# Battery_supply.net
KiCad netlist of a schematic drawn in Altium Designer
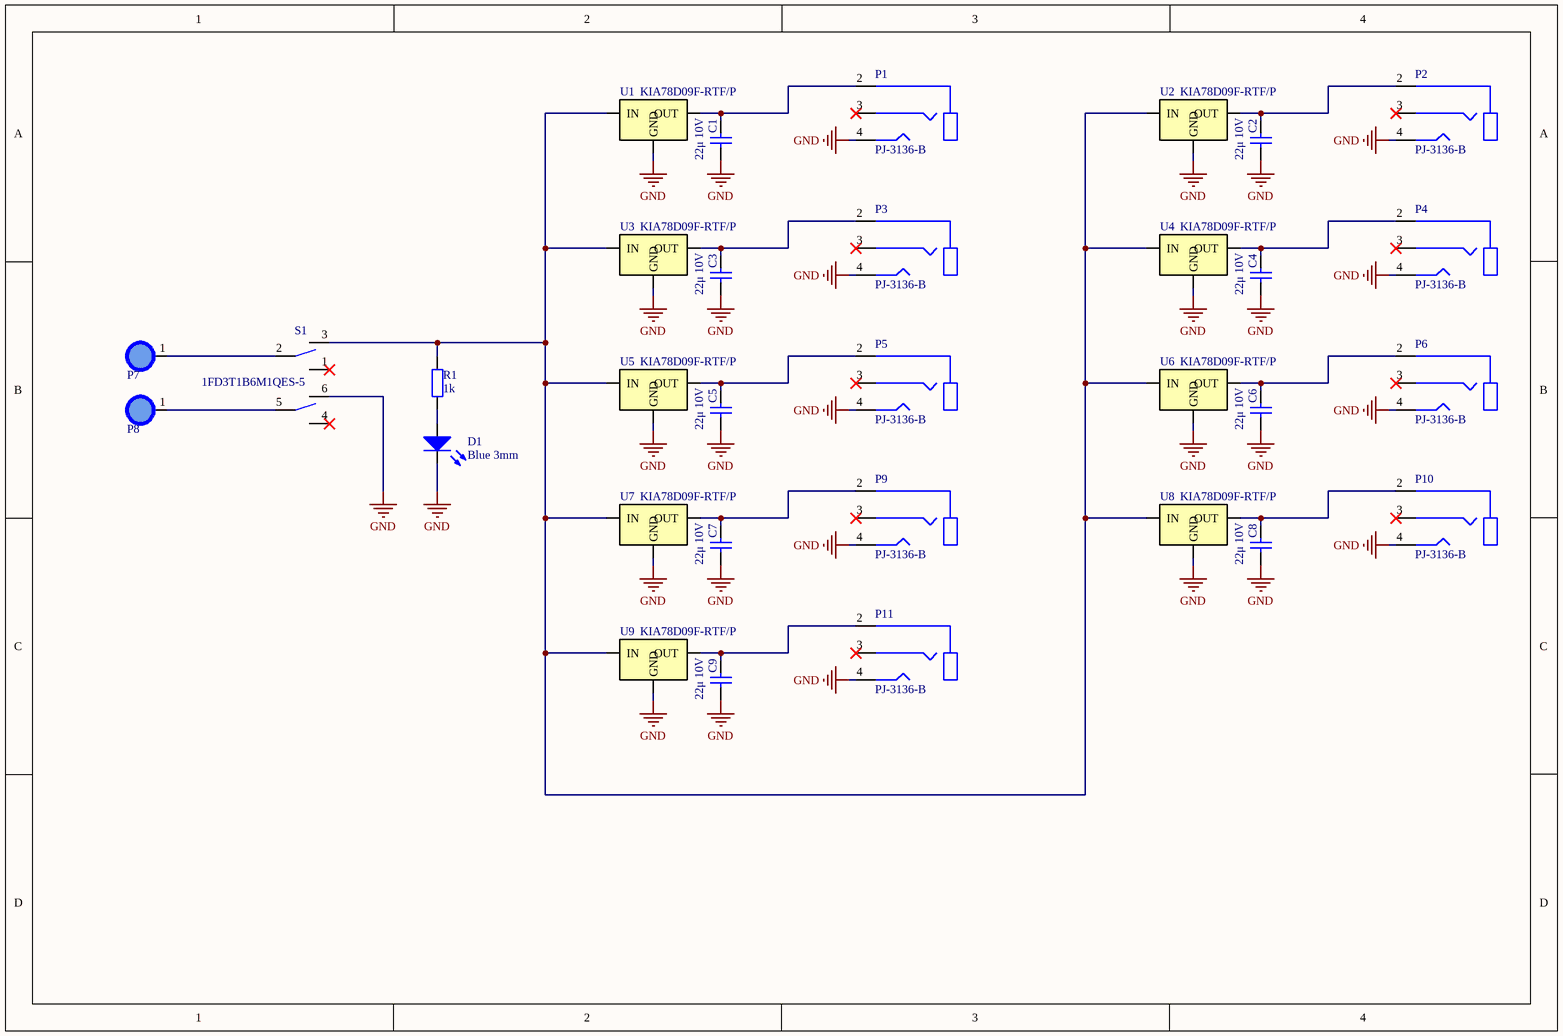
[diagram p0: Battery supply.SchDoc]

(export (version "E")
  (design (tool "Eeschema 10.0.6"))
  (components
    (comp (ref "C1")
      (value "22μ 10V")
      (footprint "Battery supply:Capacitor 0603")
      (description "X5R ±20% 10V 22uF 0603 Multilayer Ceramic Capacitors MLCC - SMD/SMT ROHS")
      (fields (field (name "MFR. PART #") "0603X226M100NT") (field (name "LCSC PART #") "C60077"))
      (libsource (lib "Battery supply") (part "Capacitor 22μF 0603 ±10% 10V"))
    )
    (comp (ref "C2")
      (value "22μ 10V")
      (footprint "Battery supply:Capacitor 0603")
      (description "X5R ±20% 10V 22uF 0603 Multilayer Ceramic Capacitors MLCC - SMD/SMT ROHS")
      (fields (field (name "MFR. PART #") "0603X226M100NT") (field (name "LCSC PART #") "C60077"))
      (libsource (lib "Battery supply") (part "Capacitor 22μF 0603 ±10% 10V"))
    )
    (comp (ref "C3")
      (value "22μ 10V")
      (footprint "Battery supply:Capacitor 0603")
      (description "X5R ±20% 10V 22uF 0603 Multilayer Ceramic Capacitors MLCC - SMD/SMT ROHS")
      (fields (field (name "MFR. PART #") "0603X226M100NT") (field (name "LCSC PART #") "C60077"))
      (libsource (lib "Battery supply") (part "Capacitor 22μF 0603 ±10% 10V"))
    )
    (comp (ref "C4")
      (value "22μ 10V")
      (footprint "Battery supply:Capacitor 0603")
      (description "X5R ±20% 10V 22uF 0603 Multilayer Ceramic Capacitors MLCC - SMD/SMT ROHS")
      (fields (field (name "MFR. PART #") "0603X226M100NT") (field (name "LCSC PART #") "C60077"))
      (libsource (lib "Battery supply") (part "Capacitor 22μF 0603 ±10% 10V"))
    )
    (comp (ref "C5")
      (value "22μ 10V")
      (footprint "Battery supply:Capacitor 0603")
      (description "X5R ±20% 10V 22uF 0603 Multilayer Ceramic Capacitors MLCC - SMD/SMT ROHS")
      (fields (field (name "MFR. PART #") "0603X226M100NT") (field (name "LCSC PART #") "C60077"))
      (libsource (lib "Battery supply") (part "Capacitor 22μF 0603 ±10% 10V"))
    )
    (comp (ref "C6")
      (value "22μ 10V")
      (footprint "Battery supply:Capacitor 0603")
      (description "X5R ±20% 10V 22uF 0603 Multilayer Ceramic Capacitors MLCC - SMD/SMT ROHS")
      (fields (field (name "MFR. PART #") "0603X226M100NT") (field (name "LCSC PART #") "C60077"))
      (libsource (lib "Battery supply") (part "Capacitor 22μF 0603 ±10% 10V"))
    )
    (comp (ref "C7")
      (value "22μ 10V")
      (footprint "Battery supply:Capacitor 0603")
      (description "X5R ±20% 10V 22uF 0603 Multilayer Ceramic Capacitors MLCC - SMD/SMT ROHS")
      (fields (field (name "MFR. PART #") "0603X226M100NT") (field (name "LCSC PART #") "C60077"))
      (libsource (lib "Battery supply") (part "Capacitor 22μF 0603 ±10% 10V"))
    )
    (comp (ref "C8")
      (value "22μ 10V")
      (footprint "Battery supply:Capacitor 0603")
      (description "X5R ±20% 10V 22uF 0603 Multilayer Ceramic Capacitors MLCC - SMD/SMT ROHS")
      (fields (field (name "MFR. PART #") "0603X226M100NT") (field (name "LCSC PART #") "C60077"))
      (libsource (lib "Battery supply") (part "Capacitor 22μF 0603 ±10% 10V"))
    )
    (comp (ref "C9")
      (value "22μ 10V")
      (footprint "Battery supply:Capacitor 0603")
      (description "X5R ±20% 10V 22uF 0603 Multilayer Ceramic Capacitors MLCC - SMD/SMT ROHS")
      (fields (field (name "MFR. PART #") "0603X226M100NT") (field (name "LCSC PART #") "C60077"))
      (libsource (lib "Battery supply") (part "Capacitor 22μF 0603 ±10% 10V"))
    )
    (comp (ref "D1")
      (value "Blue 3mm")
      (footprint "Battery supply:LED 3MM BLUE")
      (description "Blue 460nm~470nm 2.7V~3.6V Through Hole Light Emitting Diodes (LED) ROHS")
      (fields (field (name "MFR. PART #") "TJ-L3FYTGCBMCGSFLC6B-A5") (field (name "LCSC PART #") "C330760"))
      (libsource (lib "Battery supply") (part "Diode LED Blue 3mm THT"))
    )
    (comp (ref "P1")
      (value "PJ-3136-B")
      (footprint "Battery supply:PJ-3136-B")
      (description "3.5mm Plug-in headphone holder Horizontal 6 Female DIP Audio & Video Connectors ROHS")
      (fields (field (name "LCSC PART #") "C381131"))
      (libsource (lib "Battery supply") (part "Mechanical Headphone Holder JACK PJ-3136-B"))
    )
    (comp (ref "P2")
      (value "PJ-3136-B")
      (footprint "Battery supply:PJ-3136-B")
      (description "3.5mm Plug-in headphone holder Horizontal 6 Female DIP Audio & Video Connectors ROHS")
      (fields (field (name "LCSC PART #") "C381131"))
      (libsource (lib "Battery supply") (part "Mechanical Headphone Holder JACK PJ-3136-B"))
    )
    (comp (ref "P3")
      (value "PJ-3136-B")
      (footprint "Battery supply:PJ-3136-B")
      (description "3.5mm Plug-in headphone holder Horizontal 6 Female DIP Audio & Video Connectors ROHS")
      (fields (field (name "LCSC PART #") "C381131"))
      (libsource (lib "Battery supply") (part "Mechanical Headphone Holder JACK PJ-3136-B"))
    )
    (comp (ref "P4")
      (value "PJ-3136-B")
      (footprint "Battery supply:PJ-3136-B")
      (description "3.5mm Plug-in headphone holder Horizontal 6 Female DIP Audio & Video Connectors ROHS")
      (fields (field (name "LCSC PART #") "C381131"))
      (libsource (lib "Battery supply") (part "Mechanical Headphone Holder JACK PJ-3136-B"))
    )
    (comp (ref "P5")
      (value "PJ-3136-B")
      (footprint "Battery supply:PJ-3136-B")
      (description "3.5mm Plug-in headphone holder Horizontal 6 Female DIP Audio & Video Connectors ROHS")
      (fields (field (name "LCSC PART #") "C381131"))
      (libsource (lib "Battery supply") (part "Mechanical Headphone Holder JACK PJ-3136-B"))
    )
    (comp (ref "P6")
      (value "PJ-3136-B")
      (footprint "Battery supply:PJ-3136-B")
      (description "3.5mm Plug-in headphone holder Horizontal 6 Female DIP Audio & Video Connectors ROHS")
      (fields (field (name "LCSC PART #") "C381131"))
      (libsource (lib "Battery supply") (part "Mechanical Headphone Holder JACK PJ-3136-B"))
    )
    (comp (ref "P7")
      (value "PAd")
      (footprint "Battery supply:PAD")
      (description "Pad 1mm")
      (libsource (lib "Battery supply") (part "Mechanical PAD 1mm"))
    )
    (comp (ref "P8")
      (value "PAd")
      (footprint "Battery supply:PAD")
      (description "Pad 1mm")
      (libsource (lib "Battery supply") (part "Mechanical PAD 1mm"))
    )
    (comp (ref "P9")
      (value "PJ-3136-B")
      (footprint "Battery supply:PJ-3136-B")
      (description "3.5mm Plug-in headphone holder Horizontal 6 Female DIP Audio & Video Connectors ROHS")
      (fields (field (name "LCSC PART #") "C381131"))
      (libsource (lib "Battery supply") (part "Mechanical Headphone Holder JACK PJ-3136-B"))
    )
    (comp (ref "P10")
      (value "PJ-3136-B")
      (footprint "Battery supply:PJ-3136-B")
      (description "3.5mm Plug-in headphone holder Horizontal 6 Female DIP Audio & Video Connectors ROHS")
      (fields (field (name "LCSC PART #") "C381131"))
      (libsource (lib "Battery supply") (part "Mechanical Headphone Holder JACK PJ-3136-B"))
    )
    (comp (ref "P11")
      (value "PJ-3136-B")
      (footprint "Battery supply:PJ-3136-B")
      (description "3.5mm Plug-in headphone holder Horizontal 6 Female DIP Audio & Video Connectors ROHS")
      (fields (field (name "LCSC PART #") "C381131"))
      (libsource (lib "Battery supply") (part "Mechanical Headphone Holder JACK PJ-3136-B"))
    )
    (comp (ref "R1")
      (value "1k")
      (footprint "Battery supply:Resistor 0603")
      (description "±1% ±100ppm/℃ 1kΩ 0.1W 0603 Chip Resistor - Surface Mount ROHS")
      (fields (field (name "MFR. PART #") "RC0603FR-071KL") (field (name "LCSC PART #") "C22548"))
      (libsource (lib "Battery supply") (part "Resistor 1kΩ 0603 ±1% 0.1W"))
    )
    (comp (ref "S1")
      (value "1FD3T1B6M1QES-5")
      (footprint "Battery supply:1FD3T1B6M1QES-5")
      (description "H=10.5mm Toggle Switches ROHS")
      (fields (field (name "LCSC PART #") "C908278"))
      (libsource (lib "Battery supply") (part "Mechanical Toggle Switch ON-OFF-ON 1FD3T1B6M1QES-5"))
    )
    (comp (ref "U1")
      (value "KIA78D09F-RTF/P")
      (footprint "Battery supply:KIA78D09F-RTF/P")
      (description "25V 500mV @ 500mA Fixed 9V TO-252-2(DPAK) Linear Voltage Regulators (LDO) ROHS")
      (fields (field (name "LCSC PART #") "C69764"))
      (libsource (lib "Battery supply") (part "IC LDO 9V 500mA KIA78D09F-RTF/P"))
    )
    (comp (ref "U2")
      (value "KIA78D09F-RTF/P")
      (footprint "Battery supply:KIA78D09F-RTF/P")
      (description "25V 500mV @ 500mA Fixed 9V TO-252-2(DPAK) Linear Voltage Regulators (LDO) ROHS")
      (fields (field (name "LCSC PART #") "C69764"))
      (libsource (lib "Battery supply") (part "IC LDO 9V 500mA KIA78D09F-RTF/P"))
    )
    (comp (ref "U3")
      (value "KIA78D09F-RTF/P")
      (footprint "Battery supply:KIA78D09F-RTF/P")
      (description "25V 500mV @ 500mA Fixed 9V TO-252-2(DPAK) Linear Voltage Regulators (LDO) ROHS")
      (fields (field (name "LCSC PART #") "C69764"))
      (libsource (lib "Battery supply") (part "IC LDO 9V 500mA KIA78D09F-RTF/P"))
    )
    (comp (ref "U4")
      (value "KIA78D09F-RTF/P")
      (footprint "Battery supply:KIA78D09F-RTF/P")
      (description "25V 500mV @ 500mA Fixed 9V TO-252-2(DPAK) Linear Voltage Regulators (LDO) ROHS")
      (fields (field (name "LCSC PART #") "C69764"))
      (libsource (lib "Battery supply") (part "IC LDO 9V 500mA KIA78D09F-RTF/P"))
    )
    (comp (ref "U5")
      (value "KIA78D09F-RTF/P")
      (footprint "Battery supply:KIA78D09F-RTF/P")
      (description "25V 500mV @ 500mA Fixed 9V TO-252-2(DPAK) Linear Voltage Regulators (LDO) ROHS")
      (fields (field (name "LCSC PART #") "C69764"))
      (libsource (lib "Battery supply") (part "IC LDO 9V 500mA KIA78D09F-RTF/P"))
    )
    (comp (ref "U6")
      (value "KIA78D09F-RTF/P")
      (footprint "Battery supply:KIA78D09F-RTF/P")
      (description "25V 500mV @ 500mA Fixed 9V TO-252-2(DPAK) Linear Voltage Regulators (LDO) ROHS")
      (fields (field (name "LCSC PART #") "C69764"))
      (libsource (lib "Battery supply") (part "IC LDO 9V 500mA KIA78D09F-RTF/P"))
    )
    (comp (ref "U7")
      (value "KIA78D09F-RTF/P")
      (footprint "Battery supply:KIA78D09F-RTF/P")
      (description "25V 500mV @ 500mA Fixed 9V TO-252-2(DPAK) Linear Voltage Regulators (LDO) ROHS")
      (fields (field (name "LCSC PART #") "C69764"))
      (libsource (lib "Battery supply") (part "IC LDO 9V 500mA KIA78D09F-RTF/P"))
    )
    (comp (ref "U8")
      (value "KIA78D09F-RTF/P")
      (footprint "Battery supply:KIA78D09F-RTF/P")
      (description "25V 500mV @ 500mA Fixed 9V TO-252-2(DPAK) Linear Voltage Regulators (LDO) ROHS")
      (fields (field (name "LCSC PART #") "C69764"))
      (libsource (lib "Battery supply") (part "IC LDO 9V 500mA KIA78D09F-RTF/P"))
    )
    (comp (ref "U9")
      (value "KIA78D09F-RTF/P")
      (footprint "Battery supply:KIA78D09F-RTF/P")
      (description "25V 500mV @ 500mA Fixed 9V TO-252-2(DPAK) Linear Voltage Regulators (LDO) ROHS")
      (fields (field (name "LCSC PART #") "C69764"))
      (libsource (lib "Battery supply") (part "IC LDO 9V 500mA KIA78D09F-RTF/P"))
    )
  )
  (nets
    (net (code "1") (name "GND") (class "Default")
      (node (ref "C1") (pin "1") (pinfunction "1_1") (pintype "passive"))
      (node (ref "C2") (pin "1") (pinfunction "1_1") (pintype "passive"))
      (node (ref "C3") (pin "1") (pinfunction "1_1") (pintype "passive"))
      (node (ref "C4") (pin "1") (pinfunction "1_1") (pintype "passive"))
      (node (ref "C5") (pin "1") (pinfunction "1_1") (pintype "passive"))
      (node (ref "C6") (pin "1") (pinfunction "1_1") (pintype "passive"))
      (node (ref "C7") (pin "1") (pinfunction "1_1") (pintype "passive"))
      (node (ref "C8") (pin "1") (pinfunction "1_1") (pintype "passive"))
      (node (ref "C9") (pin "1") (pinfunction "1_1") (pintype "passive"))
      (node (ref "D1") (pin "1") (pinfunction "1_1") (pintype "passive"))
      (node (ref "P1") (pin "4") (pinfunction "4_4") (pintype "passive"))
      (node (ref "P10") (pin "4") (pinfunction "4_4") (pintype "passive"))
      (node (ref "P11") (pin "4") (pinfunction "4_4") (pintype "passive"))
      (node (ref "P2") (pin "4") (pinfunction "4_4") (pintype "passive"))
      (node (ref "P3") (pin "4") (pinfunction "4_4") (pintype "passive"))
      (node (ref "P4") (pin "4") (pinfunction "4_4") (pintype "passive"))
      (node (ref "P5") (pin "4") (pinfunction "4_4") (pintype "passive"))
      (node (ref "P6") (pin "4") (pinfunction "4_4") (pintype "passive"))
      (node (ref "P9") (pin "4") (pinfunction "4_4") (pintype "passive"))
      (node (ref "S1") (pin "6") (pinfunction "6_6") (pintype "passive"))
      (node (ref "U1") (pin "2") (pinfunction "GND_2") (pintype "passive"))
      (node (ref "U2") (pin "2") (pinfunction "GND_2") (pintype "passive"))
      (node (ref "U3") (pin "2") (pinfunction "GND_2") (pintype "passive"))
      (node (ref "U4") (pin "2") (pinfunction "GND_2") (pintype "passive"))
      (node (ref "U5") (pin "2") (pinfunction "GND_2") (pintype "passive"))
      (node (ref "U6") (pin "2") (pinfunction "GND_2") (pintype "passive"))
      (node (ref "U7") (pin "2") (pinfunction "GND_2") (pintype "passive"))
      (node (ref "U8") (pin "2") (pinfunction "GND_2") (pintype "passive"))
      (node (ref "U9") (pin "2") (pinfunction "GND_2") (pintype "passive"))
    )
    (net (code "2") (name "Net-(D1-Pad2)") (class "Default")
      (node (ref "D1") (pin "2") (pinfunction "2_2") (pintype "passive"))
      (node (ref "R1") (pin "1") (pinfunction "1_1") (pintype "passive"))
    )
    (net (code "3") (name "Net-(P7-Pad1)") (class "Default")
      (node (ref "P7") (pin "1") (pinfunction "1_1") (pintype "passive"))
      (node (ref "S1") (pin "2") (pinfunction "2_2") (pintype "passive"))
    )
    (net (code "4") (name "Net-(P8-Pad1)") (class "Default")
      (node (ref "P8") (pin "1") (pinfunction "1_1") (pintype "passive"))
      (node (ref "S1") (pin "5") (pinfunction "5_5") (pintype "passive"))
    )
    (net (code "5") (name "Net-(U1-IN)") (class "Default")
      (node (ref "R1") (pin "2") (pinfunction "2_2") (pintype "passive"))
      (node (ref "S1") (pin "3") (pinfunction "3_3") (pintype "passive"))
      (node (ref "U1") (pin "1") (pinfunction "IN_1") (pintype "passive"))
      (node (ref "U2") (pin "1") (pinfunction "IN_1") (pintype "passive"))
      (node (ref "U3") (pin "1") (pinfunction "IN_1") (pintype "passive"))
      (node (ref "U4") (pin "1") (pinfunction "IN_1") (pintype "passive"))
      (node (ref "U5") (pin "1") (pinfunction "IN_1") (pintype "passive"))
      (node (ref "U6") (pin "1") (pinfunction "IN_1") (pintype "passive"))
      (node (ref "U7") (pin "1") (pinfunction "IN_1") (pintype "passive"))
      (node (ref "U8") (pin "1") (pinfunction "IN_1") (pintype "passive"))
      (node (ref "U9") (pin "1") (pinfunction "IN_1") (pintype "passive"))
    )
    (net (code "6") (name "Net-(U1-OUT)") (class "Default")
      (node (ref "C1") (pin "2") (pinfunction "2_2") (pintype "passive"))
      (node (ref "P1") (pin "2") (pinfunction "2_2") (pintype "passive"))
      (node (ref "U1") (pin "3") (pinfunction "OUT_3") (pintype "passive"))
    )
    (net (code "7") (name "Net-(U2-OUT)") (class "Default")
      (node (ref "C2") (pin "2") (pinfunction "2_2") (pintype "passive"))
      (node (ref "P2") (pin "2") (pinfunction "2_2") (pintype "passive"))
      (node (ref "U2") (pin "3") (pinfunction "OUT_3") (pintype "passive"))
    )
    (net (code "8") (name "Net-(U3-OUT)") (class "Default")
      (node (ref "C3") (pin "2") (pinfunction "2_2") (pintype "passive"))
      (node (ref "P3") (pin "2") (pinfunction "2_2") (pintype "passive"))
      (node (ref "U3") (pin "3") (pinfunction "OUT_3") (pintype "passive"))
    )
    (net (code "9") (name "Net-(U4-OUT)") (class "Default")
      (node (ref "C4") (pin "2") (pinfunction "2_2") (pintype "passive"))
      (node (ref "P4") (pin "2") (pinfunction "2_2") (pintype "passive"))
      (node (ref "U4") (pin "3") (pinfunction "OUT_3") (pintype "passive"))
    )
    (net (code "10") (name "Net-(U5-OUT)") (class "Default")
      (node (ref "C5") (pin "2") (pinfunction "2_2") (pintype "passive"))
      (node (ref "P5") (pin "2") (pinfunction "2_2") (pintype "passive"))
      (node (ref "U5") (pin "3") (pinfunction "OUT_3") (pintype "passive"))
    )
    (net (code "11") (name "Net-(U6-OUT)") (class "Default")
      (node (ref "C6") (pin "2") (pinfunction "2_2") (pintype "passive"))
      (node (ref "P6") (pin "2") (pinfunction "2_2") (pintype "passive"))
      (node (ref "U6") (pin "3") (pinfunction "OUT_3") (pintype "passive"))
    )
    (net (code "12") (name "Net-(U7-OUT)") (class "Default")
      (node (ref "C7") (pin "2") (pinfunction "2_2") (pintype "passive"))
      (node (ref "P9") (pin "2") (pinfunction "2_2") (pintype "passive"))
      (node (ref "U7") (pin "3") (pinfunction "OUT_3") (pintype "passive"))
    )
    (net (code "13") (name "Net-(U8-OUT)") (class "Default")
      (node (ref "C8") (pin "2") (pinfunction "2_2") (pintype "passive"))
      (node (ref "P10") (pin "2") (pinfunction "2_2") (pintype "passive"))
      (node (ref "U8") (pin "3") (pinfunction "OUT_3") (pintype "passive"))
    )
    (net (code "14") (name "Net-(U9-OUT)") (class "Default")
      (node (ref "C9") (pin "2") (pinfunction "2_2") (pintype "passive"))
      (node (ref "P11") (pin "2") (pinfunction "2_2") (pintype "passive"))
      (node (ref "U9") (pin "3") (pinfunction "OUT_3") (pintype "passive"))
    )
    (net (code "15") (name "unconnected-(P1-Pad3)") (class "Default")
      (node (ref "P1") (pin "3") (pinfunction "3_3") (pintype "passive+no_connect"))
    )
    (net (code "16") (name "unconnected-(P2-Pad3)") (class "Default")
      (node (ref "P2") (pin "3") (pinfunction "3_3") (pintype "passive+no_connect"))
    )
    (net (code "17") (name "unconnected-(P3-Pad3)") (class "Default")
      (node (ref "P3") (pin "3") (pinfunction "3_3") (pintype "passive+no_connect"))
    )
    (net (code "18") (name "unconnected-(P4-Pad3)") (class "Default")
      (node (ref "P4") (pin "3") (pinfunction "3_3") (pintype "passive+no_connect"))
    )
    (net (code "19") (name "unconnected-(P5-Pad3)") (class "Default")
      (node (ref "P5") (pin "3") (pinfunction "3_3") (pintype "passive+no_connect"))
    )
    (net (code "20") (name "unconnected-(P6-Pad3)") (class "Default")
      (node (ref "P6") (pin "3") (pinfunction "3_3") (pintype "passive+no_connect"))
    )
    (net (code "21") (name "unconnected-(P9-Pad3)") (class "Default")
      (node (ref "P9") (pin "3") (pinfunction "3_3") (pintype "passive+no_connect"))
    )
    (net (code "22") (name "unconnected-(P10-Pad3)") (class "Default")
      (node (ref "P10") (pin "3") (pinfunction "3_3") (pintype "passive+no_connect"))
    )
    (net (code "23") (name "unconnected-(P11-Pad3)") (class "Default")
      (node (ref "P11") (pin "3") (pinfunction "3_3") (pintype "passive+no_connect"))
    )
    (net (code "24") (name "unconnected-(S1-Pad1)") (class "Default")
      (node (ref "S1") (pin "1") (pinfunction "1_1") (pintype "passive+no_connect"))
    )
    (net (code "25") (name "unconnected-(S1-Pad4)") (class "Default")
      (node (ref "S1") (pin "4") (pinfunction "4_4") (pintype "passive+no_connect"))
    )
  )
)
